# SCH_07_Filter.net
KiCad netlist of a schematic drawn in Altium Designer
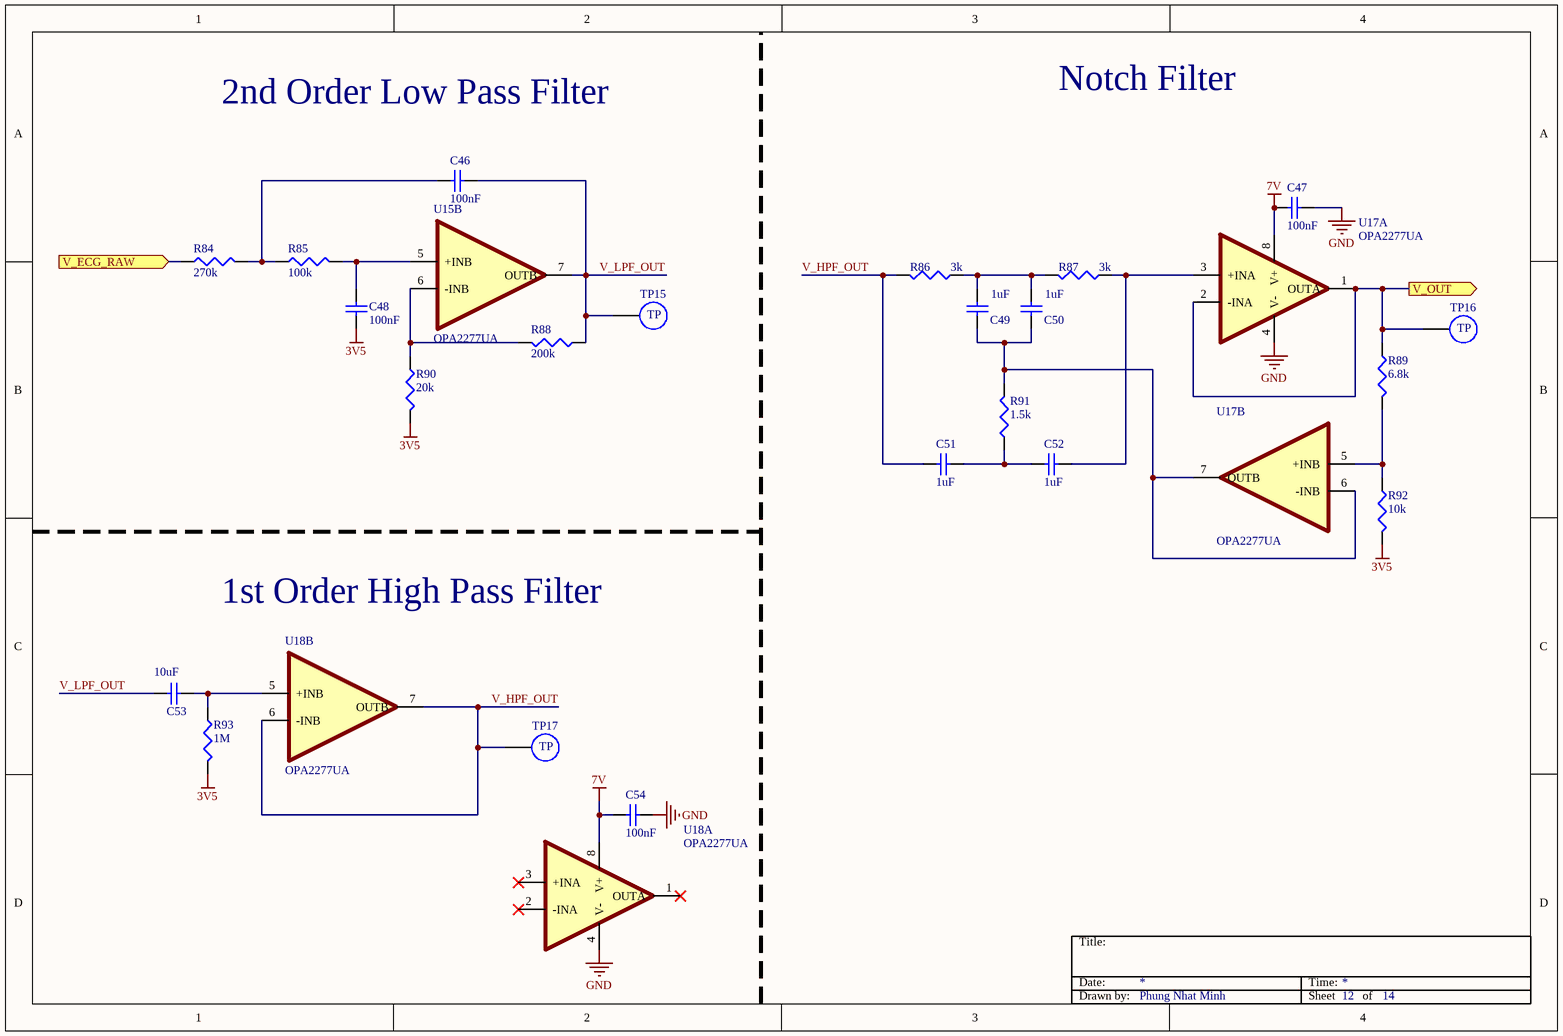
[diagram p0: SCH_07_Filter.SchDoc]

(export (version "E")
  (design (tool "Eeschema 10.0.6"))
  (components
    (comp (ref "C46")
      (value "100nF")
      (footprint "WCAP-CSGP_0603_L1.6W0.8H0.8_Reflow")
      (description "WCAP-CSGP Multilayer Ceramic Chip Capacitor, General Purpose, size 0603, X7R, 100nF, 50VDC")
      (fields
        (field (name "MANUFACTURER PART NUMBER") "885012206095")
        (field (name "MANUFACTURER") "Wurth Elektronik")
      )
      (libsource (lib "Altium_WCAP-CSGP (rev24b)") (part "885012206095"))
    )
    (comp (ref "C47")
      (value "100nF")
      (footprint "WCAP-CSGP_0603_L1.6W0.8H0.8_Reflow")
      (description "WCAP-CSGP Multilayer Ceramic Chip Capacitor, General Purpose, size 0603, X7R, 100nF, 16VDC")
      (fields
        (field (name "MANUFACTURER PART NUMBER") "885012206046")
        (field (name "MANUFACTURER") "Wurth Elektronik")
      )
      (libsource (lib "Altium_WCAP-CSGP (rev24b)") (part "885012206046"))
    )
    (comp (ref "C48")
      (value "100nF")
      (footprint "WCAP-CSGP_0603_L1.6W0.8H0.8_Reflow")
      (description "WCAP-CSGP Multilayer Ceramic Chip Capacitor, General Purpose, size 0603, X7R, 100nF, 50VDC")
      (fields
        (field (name "MANUFACTURER PART NUMBER") "885012206095")
        (field (name "MANUFACTURER") "Wurth Elektronik")
      )
      (libsource (lib "Altium_WCAP-CSGP (rev24b)") (part "885012206095"))
    )
    (comp (ref "C49")
      (value "1uF")
      (footprint "WCAP-CSGP_0603_L1.6W0.8H0.8_Reflow")
      (description "WCAP-CSGP Multilayer Ceramic Chip Capacitor, General Purpose, size 0603, X5R, 1uF, 25VDC")
      (fields
        (field (name "MANUFACTURER PART NUMBER") "885012106022")
        (field (name "MANUFACTURER") "Wurth Elektronik")
      )
      (libsource (lib "Altium_WCAP-CSGP (rev24b)") (part "885012106022"))
    )
    (comp (ref "C50")
      (value "1uF")
      (footprint "WCAP-CSGP_0603_L1.6W0.8H0.8_Reflow")
      (description "WCAP-CSGP Multilayer Ceramic Chip Capacitor, General Purpose, size 0603, X5R, 1uF, 25VDC")
      (fields
        (field (name "MANUFACTURER PART NUMBER") "885012106022")
        (field (name "MANUFACTURER") "Wurth Elektronik")
      )
      (libsource (lib "Altium_WCAP-CSGP (rev24b)") (part "885012106022"))
    )
    (comp (ref "C51")
      (value "1uF")
      (footprint "WCAP-CSGP_0603_L1.6W0.8H0.8_Reflow")
      (description "WCAP-CSGP Multilayer Ceramic Chip Capacitor, General Purpose, size 0603, X5R, 1uF, 25VDC")
      (fields
        (field (name "MANUFACTURER PART NUMBER") "885012106022")
        (field (name "MANUFACTURER") "Wurth Elektronik")
      )
      (libsource (lib "Altium_WCAP-CSGP (rev24b)") (part "885012106022"))
    )
    (comp (ref "C52")
      (value "1uF")
      (footprint "WCAP-CSGP_0603_L1.6W0.8H0.8_Reflow")
      (description "WCAP-CSGP Multilayer Ceramic Chip Capacitor, General Purpose, size 0603, X5R, 1uF, 25VDC")
      (fields
        (field (name "MANUFACTURER PART NUMBER") "885012106022")
        (field (name "MANUFACTURER") "Wurth Elektronik")
      )
      (libsource (lib "Altium_WCAP-CSGP (rev24b)") (part "885012106022"))
    )
    (comp (ref "C53")
      (value "10uF")
      (footprint "WCAP-CSGP_0603_L1.6W0.8H0.8_Reflow")
      (description "WCAP-CSGP Multilayer Ceramic Chip Capacitor, General Purpose, size 0603, X5R, 10uF, 25VDC")
      (fields
        (field (name "MANUFACTURER PART NUMBER") "885012106031")
        (field (name "MANUFACTURER") "Wurth Elektronik")
      )
      (libsource (lib "Altium_WCAP-CSGP (rev24b)") (part "885012106031"))
    )
    (comp (ref "C54")
      (value "100nF")
      (footprint "WCAP-CSGP_0603_L1.6W0.8H0.8_Reflow")
      (description "WCAP-CSGP Multilayer Ceramic Chip Capacitor, General Purpose, size 0603, X7R, 100nF, 50VDC")
      (fields
        (field (name "MANUFACTURER PART NUMBER") "885012206095")
        (field (name "MANUFACTURER") "Wurth Elektronik")
      )
      (libsource (lib "Altium_WCAP-CSGP (rev24b)") (part "885012206095"))
    )
    (comp (ref "R84")
      (value "270k")
      (footprint "WRIS-PSMB_0603_L1.6W0.8H0.35")
      (description "WRIS-PSMB Metal Plate Resistor, SMT, size 0603, 0.33W, 5mΩ, +/-1%")
      (fields
        (field (name "MANUFACTURER PART NUMBER") "580060716001")
        (field (name "MANUFACTURER") "Wurth Elektronik")
      )
      (libsource (lib "Altium_WRIS-PSMB (rev22a)") (part "580060716001"))
    )
    (comp (ref "R85")
      (value "100k")
      (footprint "WRIS-PSMB_0603_L1.6W0.8H0.35")
      (description "WRIS-PSMB Metal Plate Resistor, SMT, size 0603, 0.33W, 5mΩ, +/-1%")
      (fields
        (field (name "MANUFACTURER PART NUMBER") "580060716001")
        (field (name "MANUFACTURER") "Wurth Elektronik")
      )
      (libsource (lib "Altium_WRIS-PSMB (rev22a)") (part "580060716001"))
    )
    (comp (ref "R86")
      (value "3k")
      (footprint "WRIS-PSMB_0603_L1.6W0.8H0.35")
      (description "WRIS-PSMB Metal Plate Resistor, SMT, size 0603, 0.33W, 5mΩ, +/-1%")
      (fields
        (field (name "MANUFACTURER PART NUMBER") "580060716001")
        (field (name "MANUFACTURER") "Wurth Elektronik")
      )
      (libsource (lib "Altium_WRIS-PSMB (rev22a)") (part "580060716001"))
    )
    (comp (ref "R87")
      (value "3k")
      (footprint "WRIS-PSMB_0603_L1.6W0.8H0.35")
      (description "WRIS-PSMB Metal Plate Resistor, SMT, size 0603, 0.33W, 5mΩ, +/-1%")
      (fields
        (field (name "MANUFACTURER PART NUMBER") "580060716001")
        (field (name "MANUFACTURER") "Wurth Elektronik")
      )
      (libsource (lib "Altium_WRIS-PSMB (rev22a)") (part "580060716001"))
    )
    (comp (ref "R88")
      (value "200k")
      (footprint "WRIS-PSMB_0603_L1.6W0.8H0.35")
      (description "WRIS-PSMB Metal Plate Resistor, SMT, size 0603, 0.33W, 5mΩ, +/-1%")
      (fields
        (field (name "MANUFACTURER PART NUMBER") "580060716001")
        (field (name "MANUFACTURER") "Wurth Elektronik")
      )
      (libsource (lib "Altium_WRIS-PSMB (rev22a)") (part "580060716001"))
    )
    (comp (ref "R89")
      (value "6.8k")
      (footprint "WRIS-PSMB_0603_L1.6W0.8H0.35")
      (description "WRIS-PSMB Metal Plate Resistor, SMT, size 0603, 0.33W, 5mΩ, +/-1%")
      (fields
        (field (name "MANUFACTURER PART NUMBER") "580060716001")
        (field (name "MANUFACTURER") "Wurth Elektronik")
      )
      (libsource (lib "Altium_WRIS-PSMB (rev22a)") (part "580060716001"))
    )
    (comp (ref "R90")
      (value "20k")
      (footprint "WRIS-PSMB_0603_L1.6W0.8H0.35")
      (description "WRIS-PSMB Metal Plate Resistor, SMT, size 0603, 0.33W, 5mΩ, +/-1%")
      (fields
        (field (name "MANUFACTURER PART NUMBER") "580060716001")
        (field (name "MANUFACTURER") "Wurth Elektronik")
      )
      (libsource (lib "Altium_WRIS-PSMB (rev22a)") (part "580060716001"))
    )
    (comp (ref "R91")
      (value "1.5k")
      (footprint "WRIS-PSMB_0603_L1.6W0.8H0.35")
      (description "WRIS-PSMB Metal Plate Resistor, SMT, size 0603, 0.33W, 5mΩ, +/-1%")
      (fields
        (field (name "MANUFACTURER PART NUMBER") "580060716001")
        (field (name "MANUFACTURER") "Wurth Elektronik")
      )
      (libsource (lib "Altium_WRIS-PSMB (rev22a)") (part "580060716001"))
    )
    (comp (ref "R92")
      (value "10k")
      (footprint "WRIS-PSMB_0603_L1.6W0.8H0.35")
      (description "WRIS-PSMB Metal Plate Resistor, SMT, size 0603, 0.33W, 5mΩ, +/-1%")
      (fields
        (field (name "MANUFACTURER PART NUMBER") "580060716001")
        (field (name "MANUFACTURER") "Wurth Elektronik")
      )
      (libsource (lib "Altium_WRIS-PSMB (rev22a)") (part "580060716001"))
    )
    (comp (ref "R93")
      (value "1M")
      (footprint "WRIS-PSMB_0603_L1.6W0.8H0.35")
      (description "WRIS-PSMB Metal Plate Resistor, SMT, size 0603, 0.33W, 5mΩ, +/-1%")
      (fields
        (field (name "MANUFACTURER PART NUMBER") "580060716001")
        (field (name "MANUFACTURER") "Wurth Elektronik")
      )
      (libsource (lib "Altium_WRIS-PSMB (rev22a)") (part "580060716001"))
    )
    (comp (ref "TP15")
      (value "Pad_Test_Point")
      (footprint "Pad_Test_Point")
      (libsource (lib "Test_Point") (part "Pad_Test_Point"))
    )
    (comp (ref "TP16")
      (value "Pad_Test_Point")
      (footprint "Pad_Test_Point")
      (libsource (lib "Test_Point") (part "Pad_Test_Point"))
    )
    (comp (ref "TP17")
      (value "Pad_Test_Point")
      (footprint "Pad_Test_Point")
      (libsource (lib "Test_Point") (part "Pad_Test_Point"))
    )
    (comp (ref "U15")
      (value "OPA2277UA")
      (footprint "SOIC127P599X175-8N")
      (fields (field (name "MP") "OPA2227UA"))
      (libsource (lib "OPA2277") (part "OPA2277UA"))
    )
    (comp (ref "U17")
      (value "OPA2277UA")
      (footprint "SOIC127P599X175-8N")
      (fields (field (name "MP") "OPA2227UA"))
      (libsource (lib "OPA2277") (part "OPA2277UA"))
    )
    (comp (ref "U18")
      (value "OPA2277UA")
      (footprint "SOIC127P599X175-8N")
      (fields (field (name "MP") "OPA2227UA"))
      (libsource (lib "OPA2277") (part "OPA2277UA"))
    )
  )
  (nets
    (net (code "1") (name "/V_ECG_RAW") (class "Default")
      (node (ref "R84") (pin "1") (pinfunction "1_1") (pintype "passive"))
    )
    (net (code "2") (name "/V_HPF_OUT") (class "Default")
      (node (ref "C51") (pin "2") (pinfunction "2_2") (pintype "passive"))
      (node (ref "R86") (pin "2") (pinfunction "2_2") (pintype "passive"))
      (node (ref "TP17") (pin "1") (pinfunction "1_1") (pintype "passive"))
      (node (ref "U18") (pin "6") (pinfunction "-INB_6") (pintype "passive"))
      (node (ref "U18") (pin "7") (pinfunction "OUTB_7") (pintype "passive"))
    )
    (net (code "3") (name "/V_LPF_OUT") (class "Default")
      (node (ref "C46") (pin "1") (pinfunction "1_1") (pintype "passive"))
      (node (ref "C53") (pin "1") (pinfunction "1_1") (pintype "passive"))
      (node (ref "R88") (pin "1") (pinfunction "1_1") (pintype "passive"))
      (node (ref "TP15") (pin "1") (pinfunction "1_1") (pintype "passive"))
      (node (ref "U15") (pin "7") (pinfunction "OUTB_7") (pintype "passive"))
    )
    (net (code "4") (name "/V_OUT") (class "Default")
      (node (ref "R89") (pin "1") (pinfunction "1_1") (pintype "passive"))
      (node (ref "TP16") (pin "1") (pinfunction "1_1") (pintype "passive"))
      (node (ref "U17") (pin "1") (pinfunction "OUTA_1") (pintype "passive"))
      (node (ref "U17") (pin "2") (pinfunction "-INA_2") (pintype "passive"))
    )
    (net (code "5") (name "3V5") (class "Default")
      (node (ref "C48") (pin "1") (pinfunction "1_1") (pintype "passive"))
      (node (ref "R90") (pin "2") (pinfunction "2_2") (pintype "passive"))
      (node (ref "R92") (pin "2") (pinfunction "2_2") (pintype "passive"))
      (node (ref "R93") (pin "2") (pinfunction "2_2") (pintype "passive"))
    )
    (net (code "6") (name "7V") (class "Default")
      (node (ref "C47") (pin "2") (pinfunction "2_2") (pintype "passive"))
      (node (ref "C54") (pin "2") (pinfunction "2_2") (pintype "passive"))
      (node (ref "U17") (pin "8") (pinfunction "V+_8") (pintype "power_in"))
      (node (ref "U18") (pin "8") (pinfunction "V+_8") (pintype "power_in"))
    )
    (net (code "7") (name "GND") (class "Default")
      (node (ref "C47") (pin "1") (pinfunction "1_1") (pintype "passive"))
      (node (ref "C54") (pin "1") (pinfunction "1_1") (pintype "passive"))
      (node (ref "U17") (pin "4") (pinfunction "V-_4") (pintype "power_in"))
      (node (ref "U18") (pin "4") (pinfunction "V-_4") (pintype "power_in"))
    )
    (net (code "8") (name "Net-(C46-Pad2)") (class "Default")
      (node (ref "C46") (pin "2") (pinfunction "2_2") (pintype "passive"))
      (node (ref "R84") (pin "2") (pinfunction "2_2") (pintype "passive"))
      (node (ref "R85") (pin "1") (pinfunction "1_1") (pintype "passive"))
    )
    (net (code "9") (name "Net-(C49-Pad2)") (class "Default")
      (node (ref "C49") (pin "2") (pinfunction "2_2") (pintype "passive"))
      (node (ref "C50") (pin "2") (pinfunction "2_2") (pintype "passive"))
      (node (ref "R86") (pin "1") (pinfunction "1_1") (pintype "passive"))
      (node (ref "R87") (pin "2") (pinfunction "2_2") (pintype "passive"))
    )
    (net (code "10") (name "Net-(C51-Pad1)") (class "Default")
      (node (ref "C51") (pin "1") (pinfunction "1_1") (pintype "passive"))
      (node (ref "C52") (pin "2") (pinfunction "2_2") (pintype "passive"))
      (node (ref "R91") (pin "1") (pinfunction "1_1") (pintype "passive"))
    )
    (net (code "11") (name "Net-(U15B-+INB)") (class "Default")
      (node (ref "C48") (pin "2") (pinfunction "2_2") (pintype "passive"))
      (node (ref "R85") (pin "2") (pinfunction "2_2") (pintype "passive"))
      (node (ref "U15") (pin "5") (pinfunction "+INB_5") (pintype "passive"))
    )
    (net (code "12") (name "Net-(U15B--INB)") (class "Default")
      (node (ref "R88") (pin "2") (pinfunction "2_2") (pintype "passive"))
      (node (ref "R90") (pin "1") (pinfunction "1_1") (pintype "passive"))
      (node (ref "U15") (pin "6") (pinfunction "-INB_6") (pintype "passive"))
    )
    (net (code "13") (name "Net-(U17A-+INA)") (class "Default")
      (node (ref "C52") (pin "1") (pinfunction "1_1") (pintype "passive"))
      (node (ref "R87") (pin "1") (pinfunction "1_1") (pintype "passive"))
      (node (ref "U17") (pin "3") (pinfunction "+INA_3") (pintype "passive"))
    )
    (net (code "14") (name "Net-(U17B-+INB)") (class "Default")
      (node (ref "R89") (pin "2") (pinfunction "2_2") (pintype "passive"))
      (node (ref "R92") (pin "1") (pinfunction "1_1") (pintype "passive"))
      (node (ref "U17") (pin "5") (pinfunction "+INB_5") (pintype "passive"))
    )
    (net (code "15") (name "Net-(U17B--INB)") (class "Default")
      (node (ref "C49") (pin "1") (pinfunction "1_1") (pintype "passive"))
      (node (ref "C50") (pin "1") (pinfunction "1_1") (pintype "passive"))
      (node (ref "R91") (pin "2") (pinfunction "2_2") (pintype "passive"))
      (node (ref "U17") (pin "6") (pinfunction "-INB_6") (pintype "passive"))
      (node (ref "U17") (pin "7") (pinfunction "OUTB_7") (pintype "passive"))
    )
    (net (code "16") (name "Net-(U18B-+INB)") (class "Default")
      (node (ref "C53") (pin "2") (pinfunction "2_2") (pintype "passive"))
      (node (ref "R93") (pin "1") (pinfunction "1_1") (pintype "passive"))
      (node (ref "U18") (pin "5") (pinfunction "+INB_5") (pintype "passive"))
    )
    (net (code "17") (name "unconnected-(U18A-+INA-Pad3)") (class "Default")
      (node (ref "U18") (pin "3") (pinfunction "+INA_3") (pintype "passive+no_connect"))
    )
    (net (code "18") (name "unconnected-(U18A--INA-Pad2)") (class "Default")
      (node (ref "U18") (pin "2") (pinfunction "-INA_2") (pintype "passive+no_connect"))
    )
    (net (code "19") (name "unconnected-(U18A-OUTA-Pad1)") (class "Default")
      (node (ref "U18") (pin "1") (pinfunction "OUTA_1") (pintype "passive+no_connect"))
    )
  )
)
